# Input2.net
KiCad netlist of a schematic drawn in Altium Designer
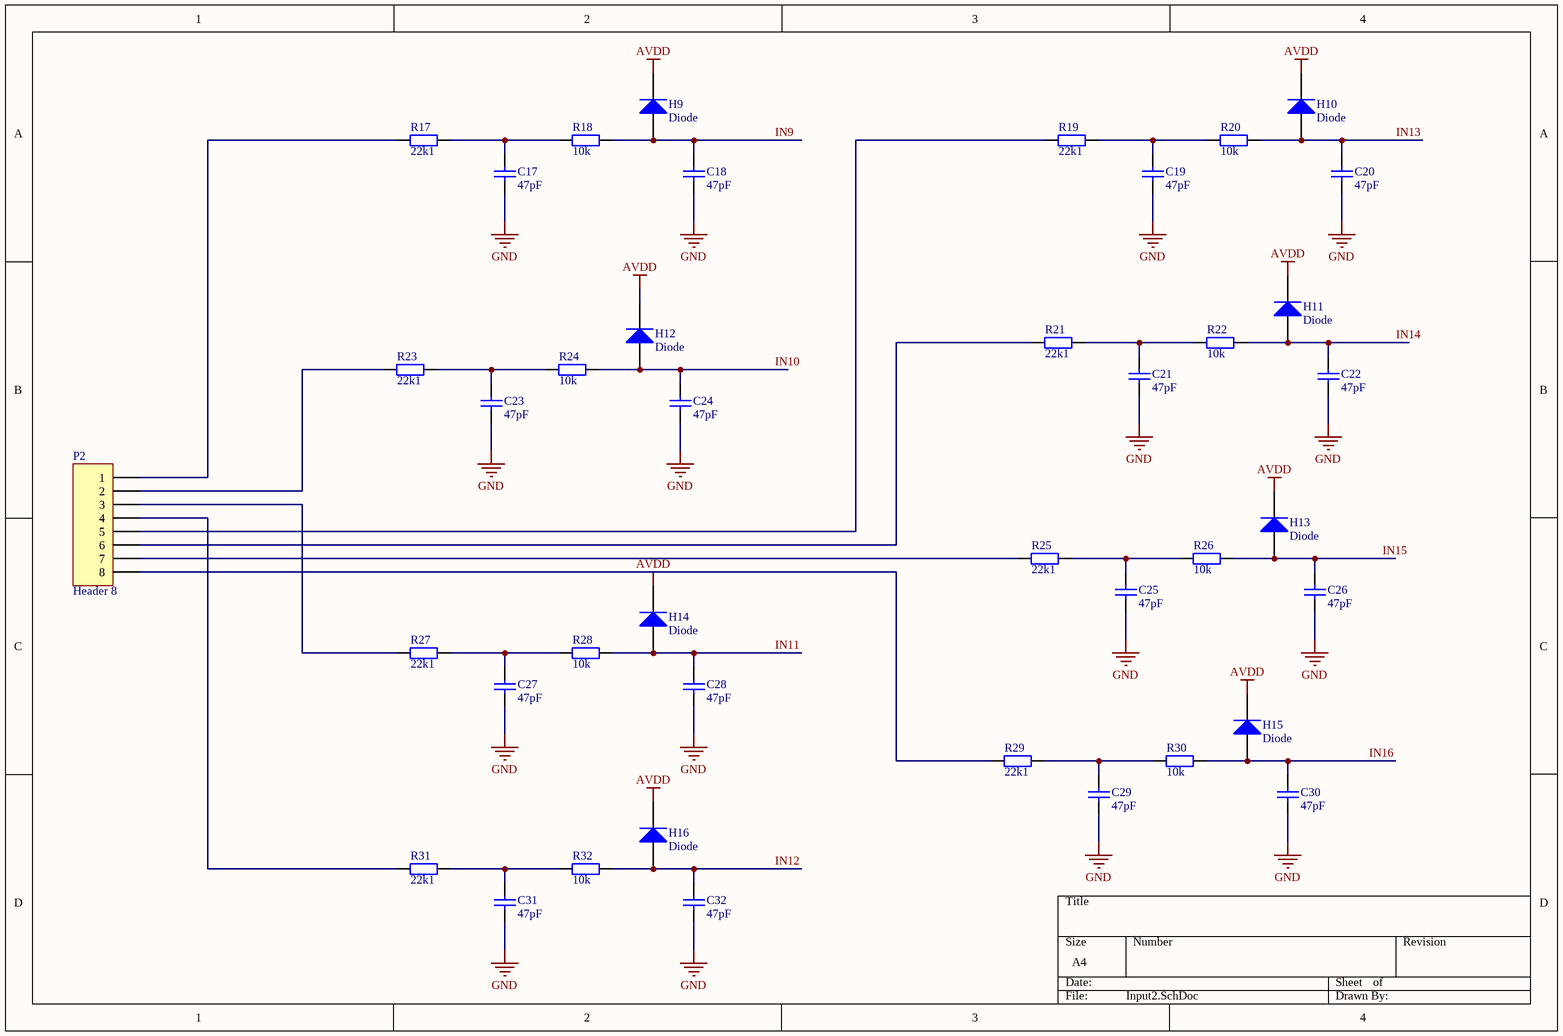
[diagram p0: Input2.SchDoc]

(export (version "E")
  (design (tool "Eeschema 10.0.6"))
  (components
    (comp (ref "C17")
      (value "47pF")
      (footprint "RAD-0.3")
      (description "Capacitor")
      (fields (field (name "PUBLISHER") "Altium Limited"))
      (libsource (lib "Miscellaneous Devices") (part "Cap"))
    )
    (comp (ref "C18")
      (value "47pF")
      (footprint "RAD-0.3")
      (description "Capacitor")
      (fields (field (name "PUBLISHER") "Altium Limited"))
      (libsource (lib "Miscellaneous Devices") (part "Cap"))
    )
    (comp (ref "C19")
      (value "47pF")
      (footprint "RAD-0.3")
      (description "Capacitor")
      (fields (field (name "PUBLISHER") "Altium Limited"))
      (libsource (lib "Miscellaneous Devices") (part "Cap"))
    )
    (comp (ref "C20")
      (value "47pF")
      (footprint "RAD-0.3")
      (description "Capacitor")
      (fields (field (name "PUBLISHER") "Altium Limited"))
      (libsource (lib "Miscellaneous Devices") (part "Cap"))
    )
    (comp (ref "C21")
      (value "47pF")
      (footprint "RAD-0.3")
      (description "Capacitor")
      (fields (field (name "PUBLISHER") "Altium Limited"))
      (libsource (lib "Miscellaneous Devices") (part "Cap"))
    )
    (comp (ref "C22")
      (value "47pF")
      (footprint "RAD-0.3")
      (description "Capacitor")
      (fields (field (name "PUBLISHER") "Altium Limited"))
      (libsource (lib "Miscellaneous Devices") (part "Cap"))
    )
    (comp (ref "C23")
      (value "47pF")
      (footprint "RAD-0.3")
      (description "Capacitor")
      (fields (field (name "PUBLISHER") "Altium Limited"))
      (libsource (lib "Miscellaneous Devices") (part "Cap"))
    )
    (comp (ref "C24")
      (value "47pF")
      (footprint "RAD-0.3")
      (description "Capacitor")
      (fields (field (name "PUBLISHER") "Altium Limited"))
      (libsource (lib "Miscellaneous Devices") (part "Cap"))
    )
    (comp (ref "C25")
      (value "47pF")
      (footprint "RAD-0.3")
      (description "Capacitor")
      (fields (field (name "PUBLISHER") "Altium Limited"))
      (libsource (lib "Miscellaneous Devices") (part "Cap"))
    )
    (comp (ref "C26")
      (value "47pF")
      (footprint "RAD-0.3")
      (description "Capacitor")
      (fields (field (name "PUBLISHER") "Altium Limited"))
      (libsource (lib "Miscellaneous Devices") (part "Cap"))
    )
    (comp (ref "C27")
      (value "47pF")
      (footprint "RAD-0.3")
      (description "Capacitor")
      (fields (field (name "PUBLISHER") "Altium Limited"))
      (libsource (lib "Miscellaneous Devices") (part "Cap"))
    )
    (comp (ref "C28")
      (value "47pF")
      (footprint "RAD-0.3")
      (description "Capacitor")
      (fields (field (name "PUBLISHER") "Altium Limited"))
      (libsource (lib "Miscellaneous Devices") (part "Cap"))
    )
    (comp (ref "C29")
      (value "47pF")
      (footprint "RAD-0.3")
      (description "Capacitor")
      (fields (field (name "PUBLISHER") "Altium Limited"))
      (libsource (lib "Miscellaneous Devices") (part "Cap"))
    )
    (comp (ref "C30")
      (value "47pF")
      (footprint "RAD-0.3")
      (description "Capacitor")
      (fields (field (name "PUBLISHER") "Altium Limited"))
      (libsource (lib "Miscellaneous Devices") (part "Cap"))
    )
    (comp (ref "C31")
      (value "47pF")
      (footprint "RAD-0.3")
      (description "Capacitor")
      (fields (field (name "PUBLISHER") "Altium Limited"))
      (libsource (lib "Miscellaneous Devices") (part "Cap"))
    )
    (comp (ref "C32")
      (value "47pF")
      (footprint "RAD-0.3")
      (description "Capacitor")
      (fields (field (name "PUBLISHER") "Altium Limited"))
      (libsource (lib "Miscellaneous Devices") (part "Cap"))
    )
    (comp (ref "H9")
      (value "Diode")
      (footprint "SMC")
      (description "Default Diode")
      (fields (field (name "PUBLISHER") "Altium Limited"))
      (libsource (lib "Miscellaneous Devices") (part "Diode"))
    )
    (comp (ref "H10")
      (value "Diode")
      (footprint "SMC")
      (description "Default Diode")
      (fields (field (name "PUBLISHER") "Altium Limited"))
      (libsource (lib "Miscellaneous Devices") (part "Diode"))
    )
    (comp (ref "H11")
      (value "Diode")
      (footprint "SMC")
      (description "Default Diode")
      (fields (field (name "PUBLISHER") "Altium Limited"))
      (libsource (lib "Miscellaneous Devices") (part "Diode"))
    )
    (comp (ref "H12")
      (value "Diode")
      (footprint "SMC")
      (description "Default Diode")
      (fields (field (name "PUBLISHER") "Altium Limited"))
      (libsource (lib "Miscellaneous Devices") (part "Diode"))
    )
    (comp (ref "H13")
      (value "Diode")
      (footprint "SMC")
      (description "Default Diode")
      (fields (field (name "PUBLISHER") "Altium Limited"))
      (libsource (lib "Miscellaneous Devices") (part "Diode"))
    )
    (comp (ref "H14")
      (value "Diode")
      (footprint "SMC")
      (description "Default Diode")
      (fields (field (name "PUBLISHER") "Altium Limited"))
      (libsource (lib "Miscellaneous Devices") (part "Diode"))
    )
    (comp (ref "H15")
      (value "Diode")
      (footprint "SMC")
      (description "Default Diode")
      (fields (field (name "PUBLISHER") "Altium Limited"))
      (libsource (lib "Miscellaneous Devices") (part "Diode"))
    )
    (comp (ref "H16")
      (value "Diode")
      (footprint "SMC")
      (description "Default Diode")
      (fields (field (name "PUBLISHER") "Altium Limited"))
      (libsource (lib "Miscellaneous Devices") (part "Diode"))
    )
    (comp (ref "P2")
      (value "Header 8")
      (footprint "HDR1X8")
      (description "Header, 8-Pin")
      (fields (field (name "PUBLISHER") "Altium Limited"))
      (libsource (lib "Miscellaneous Connectors") (part "Header 8"))
    )
    (comp (ref "R17")
      (value "22k1")
      (footprint "AXIAL-0.4")
      (description "Resistor")
      (fields (field (name "PUBLISHER") "Altium Limited"))
      (libsource (lib "Miscellaneous Devices") (part "Res2"))
    )
    (comp (ref "R18")
      (value "10k")
      (footprint "AXIAL-0.4")
      (description "Resistor")
      (fields (field (name "PUBLISHER") "Altium Limited"))
      (libsource (lib "Miscellaneous Devices") (part "Res2"))
    )
    (comp (ref "R19")
      (value "22k1")
      (footprint "AXIAL-0.4")
      (description "Resistor")
      (fields (field (name "PUBLISHER") "Altium Limited"))
      (libsource (lib "Miscellaneous Devices") (part "Res2"))
    )
    (comp (ref "R20")
      (value "10k")
      (footprint "AXIAL-0.4")
      (description "Resistor")
      (fields (field (name "PUBLISHER") "Altium Limited"))
      (libsource (lib "Miscellaneous Devices") (part "Res2"))
    )
    (comp (ref "R21")
      (value "22k1")
      (footprint "AXIAL-0.4")
      (description "Resistor")
      (fields (field (name "PUBLISHER") "Altium Limited"))
      (libsource (lib "Miscellaneous Devices") (part "Res2"))
    )
    (comp (ref "R22")
      (value "10k")
      (footprint "AXIAL-0.4")
      (description "Resistor")
      (fields (field (name "PUBLISHER") "Altium Limited"))
      (libsource (lib "Miscellaneous Devices") (part "Res2"))
    )
    (comp (ref "R23")
      (value "22k1")
      (footprint "AXIAL-0.4")
      (description "Resistor")
      (fields (field (name "PUBLISHER") "Altium Limited"))
      (libsource (lib "Miscellaneous Devices") (part "Res2"))
    )
    (comp (ref "R24")
      (value "10k")
      (footprint "AXIAL-0.4")
      (description "Resistor")
      (fields (field (name "PUBLISHER") "Altium Limited"))
      (libsource (lib "Miscellaneous Devices") (part "Res2"))
    )
    (comp (ref "R25")
      (value "22k1")
      (footprint "AXIAL-0.4")
      (description "Resistor")
      (fields (field (name "PUBLISHER") "Altium Limited"))
      (libsource (lib "Miscellaneous Devices") (part "Res2"))
    )
    (comp (ref "R26")
      (value "10k")
      (footprint "AXIAL-0.4")
      (description "Resistor")
      (fields (field (name "PUBLISHER") "Altium Limited"))
      (libsource (lib "Miscellaneous Devices") (part "Res2"))
    )
    (comp (ref "R27")
      (value "22k1")
      (footprint "AXIAL-0.4")
      (description "Resistor")
      (fields (field (name "PUBLISHER") "Altium Limited"))
      (libsource (lib "Miscellaneous Devices") (part "Res2"))
    )
    (comp (ref "R28")
      (value "10k")
      (footprint "AXIAL-0.4")
      (description "Resistor")
      (fields (field (name "PUBLISHER") "Altium Limited"))
      (libsource (lib "Miscellaneous Devices") (part "Res2"))
    )
    (comp (ref "R29")
      (value "22k1")
      (footprint "AXIAL-0.4")
      (description "Resistor")
      (fields (field (name "PUBLISHER") "Altium Limited"))
      (libsource (lib "Miscellaneous Devices") (part "Res2"))
    )
    (comp (ref "R30")
      (value "10k")
      (footprint "AXIAL-0.4")
      (description "Resistor")
      (fields (field (name "PUBLISHER") "Altium Limited"))
      (libsource (lib "Miscellaneous Devices") (part "Res2"))
    )
    (comp (ref "R31")
      (value "22k1")
      (footprint "AXIAL-0.4")
      (description "Resistor")
      (fields (field (name "PUBLISHER") "Altium Limited"))
      (libsource (lib "Miscellaneous Devices") (part "Res2"))
    )
    (comp (ref "R32")
      (value "10k")
      (footprint "AXIAL-0.4")
      (description "Resistor")
      (fields (field (name "PUBLISHER") "Altium Limited"))
      (libsource (lib "Miscellaneous Devices") (part "Res2"))
    )
  )
  (nets
    (net (code "1") (name "/IN9") (class "Default")
      (node (ref "C18") (pin "2") (pinfunction "2_2") (pintype "passive"))
      (node (ref "H9") (pin "1") (pinfunction "A_1") (pintype "passive"))
      (node (ref "R18") (pin "2") (pinfunction "2_2") (pintype "passive"))
    )
    (net (code "2") (name "/IN10") (class "Default")
      (node (ref "C24") (pin "2") (pinfunction "2_2") (pintype "passive"))
      (node (ref "H12") (pin "1") (pinfunction "A_1") (pintype "passive"))
      (node (ref "R24") (pin "2") (pinfunction "2_2") (pintype "passive"))
    )
    (net (code "3") (name "/IN11") (class "Default")
      (node (ref "C28") (pin "2") (pinfunction "2_2") (pintype "passive"))
      (node (ref "H14") (pin "1") (pinfunction "A_1") (pintype "passive"))
      (node (ref "R28") (pin "2") (pinfunction "2_2") (pintype "passive"))
    )
    (net (code "4") (name "/IN12") (class "Default")
      (node (ref "C32") (pin "2") (pinfunction "2_2") (pintype "passive"))
      (node (ref "H16") (pin "1") (pinfunction "A_1") (pintype "passive"))
      (node (ref "R32") (pin "2") (pinfunction "2_2") (pintype "passive"))
    )
    (net (code "5") (name "/IN13") (class "Default")
      (node (ref "C20") (pin "2") (pinfunction "2_2") (pintype "passive"))
      (node (ref "H10") (pin "1") (pinfunction "A_1") (pintype "passive"))
      (node (ref "R20") (pin "2") (pinfunction "2_2") (pintype "passive"))
    )
    (net (code "6") (name "/IN14") (class "Default")
      (node (ref "C22") (pin "2") (pinfunction "2_2") (pintype "passive"))
      (node (ref "H11") (pin "1") (pinfunction "A_1") (pintype "passive"))
      (node (ref "R22") (pin "2") (pinfunction "2_2") (pintype "passive"))
    )
    (net (code "7") (name "/IN15") (class "Default")
      (node (ref "C26") (pin "2") (pinfunction "2_2") (pintype "passive"))
      (node (ref "H13") (pin "1") (pinfunction "A_1") (pintype "passive"))
      (node (ref "R26") (pin "2") (pinfunction "2_2") (pintype "passive"))
    )
    (net (code "8") (name "/IN16") (class "Default")
      (node (ref "C30") (pin "2") (pinfunction "2_2") (pintype "passive"))
      (node (ref "H15") (pin "1") (pinfunction "A_1") (pintype "passive"))
      (node (ref "R30") (pin "2") (pinfunction "2_2") (pintype "passive"))
    )
    (net (code "9") (name "AVDD") (class "Default")
      (node (ref "H10") (pin "2") (pinfunction "K_2") (pintype "passive"))
      (node (ref "H11") (pin "2") (pinfunction "K_2") (pintype "passive"))
      (node (ref "H12") (pin "2") (pinfunction "K_2") (pintype "passive"))
      (node (ref "H13") (pin "2") (pinfunction "K_2") (pintype "passive"))
      (node (ref "H14") (pin "2") (pinfunction "K_2") (pintype "passive"))
      (node (ref "H15") (pin "2") (pinfunction "K_2") (pintype "passive"))
      (node (ref "H16") (pin "2") (pinfunction "K_2") (pintype "passive"))
      (node (ref "H9") (pin "2") (pinfunction "K_2") (pintype "passive"))
    )
    (net (code "10") (name "GND") (class "Default")
      (node (ref "C17") (pin "1") (pinfunction "1_1") (pintype "passive"))
      (node (ref "C18") (pin "1") (pinfunction "1_1") (pintype "passive"))
      (node (ref "C19") (pin "1") (pinfunction "1_1") (pintype "passive"))
      (node (ref "C20") (pin "1") (pinfunction "1_1") (pintype "passive"))
      (node (ref "C21") (pin "1") (pinfunction "1_1") (pintype "passive"))
      (node (ref "C22") (pin "1") (pinfunction "1_1") (pintype "passive"))
      (node (ref "C23") (pin "1") (pinfunction "1_1") (pintype "passive"))
      (node (ref "C24") (pin "1") (pinfunction "1_1") (pintype "passive"))
      (node (ref "C25") (pin "1") (pinfunction "1_1") (pintype "passive"))
      (node (ref "C26") (pin "1") (pinfunction "1_1") (pintype "passive"))
      (node (ref "C27") (pin "1") (pinfunction "1_1") (pintype "passive"))
      (node (ref "C28") (pin "1") (pinfunction "1_1") (pintype "passive"))
      (node (ref "C29") (pin "1") (pinfunction "1_1") (pintype "passive"))
      (node (ref "C30") (pin "1") (pinfunction "1_1") (pintype "passive"))
      (node (ref "C31") (pin "1") (pinfunction "1_1") (pintype "passive"))
      (node (ref "C32") (pin "1") (pinfunction "1_1") (pintype "passive"))
    )
    (net (code "11") (name "Net-(C17-Pad2)") (class "Default")
      (node (ref "C17") (pin "2") (pinfunction "2_2") (pintype "passive"))
      (node (ref "R17") (pin "2") (pinfunction "2_2") (pintype "passive"))
      (node (ref "R18") (pin "1") (pinfunction "1_1") (pintype "passive"))
    )
    (net (code "12") (name "Net-(C19-Pad2)") (class "Default")
      (node (ref "C19") (pin "2") (pinfunction "2_2") (pintype "passive"))
      (node (ref "R19") (pin "2") (pinfunction "2_2") (pintype "passive"))
      (node (ref "R20") (pin "1") (pinfunction "1_1") (pintype "passive"))
    )
    (net (code "13") (name "Net-(C21-Pad2)") (class "Default")
      (node (ref "C21") (pin "2") (pinfunction "2_2") (pintype "passive"))
      (node (ref "R21") (pin "2") (pinfunction "2_2") (pintype "passive"))
      (node (ref "R22") (pin "1") (pinfunction "1_1") (pintype "passive"))
    )
    (net (code "14") (name "Net-(C23-Pad2)") (class "Default")
      (node (ref "C23") (pin "2") (pinfunction "2_2") (pintype "passive"))
      (node (ref "R23") (pin "2") (pinfunction "2_2") (pintype "passive"))
      (node (ref "R24") (pin "1") (pinfunction "1_1") (pintype "passive"))
    )
    (net (code "15") (name "Net-(C25-Pad2)") (class "Default")
      (node (ref "C25") (pin "2") (pinfunction "2_2") (pintype "passive"))
      (node (ref "R25") (pin "2") (pinfunction "2_2") (pintype "passive"))
      (node (ref "R26") (pin "1") (pinfunction "1_1") (pintype "passive"))
    )
    (net (code "16") (name "Net-(C27-Pad2)") (class "Default")
      (node (ref "C27") (pin "2") (pinfunction "2_2") (pintype "passive"))
      (node (ref "R27") (pin "2") (pinfunction "2_2") (pintype "passive"))
      (node (ref "R28") (pin "1") (pinfunction "1_1") (pintype "passive"))
    )
    (net (code "17") (name "Net-(C29-Pad2)") (class "Default")
      (node (ref "C29") (pin "2") (pinfunction "2_2") (pintype "passive"))
      (node (ref "R29") (pin "2") (pinfunction "2_2") (pintype "passive"))
      (node (ref "R30") (pin "1") (pinfunction "1_1") (pintype "passive"))
    )
    (net (code "18") (name "Net-(C31-Pad2)") (class "Default")
      (node (ref "C31") (pin "2") (pinfunction "2_2") (pintype "passive"))
      (node (ref "R31") (pin "2") (pinfunction "2_2") (pintype "passive"))
      (node (ref "R32") (pin "1") (pinfunction "1_1") (pintype "passive"))
    )
    (net (code "19") (name "Net-(P2-Pad1)") (class "Default")
      (node (ref "P2") (pin "1") (pinfunction "1_1") (pintype "passive"))
      (node (ref "R17") (pin "1") (pinfunction "1_1") (pintype "passive"))
    )
    (net (code "20") (name "Net-(P2-Pad2)") (class "Default")
      (node (ref "P2") (pin "2") (pinfunction "2_2") (pintype "passive"))
      (node (ref "R23") (pin "1") (pinfunction "1_1") (pintype "passive"))
    )
    (net (code "21") (name "Net-(P2-Pad3)") (class "Default")
      (node (ref "P2") (pin "3") (pinfunction "3_3") (pintype "passive"))
      (node (ref "R27") (pin "1") (pinfunction "1_1") (pintype "passive"))
    )
    (net (code "22") (name "Net-(P2-Pad4)") (class "Default")
      (node (ref "P2") (pin "4") (pinfunction "4_4") (pintype "passive"))
      (node (ref "R31") (pin "1") (pinfunction "1_1") (pintype "passive"))
    )
    (net (code "23") (name "Net-(P2-Pad5)") (class "Default")
      (node (ref "P2") (pin "5") (pinfunction "5_5") (pintype "passive"))
      (node (ref "R19") (pin "1") (pinfunction "1_1") (pintype "passive"))
    )
    (net (code "24") (name "Net-(P2-Pad6)") (class "Default")
      (node (ref "P2") (pin "6") (pinfunction "6_6") (pintype "passive"))
      (node (ref "R21") (pin "1") (pinfunction "1_1") (pintype "passive"))
    )
    (net (code "25") (name "Net-(P2-Pad7)") (class "Default")
      (node (ref "P2") (pin "7") (pinfunction "7_7") (pintype "passive"))
      (node (ref "R25") (pin "1") (pinfunction "1_1") (pintype "passive"))
    )
    (net (code "26") (name "Net-(P2-Pad8)") (class "Default")
      (node (ref "P2") (pin "8") (pinfunction "8_8") (pintype "passive"))
      (node (ref "R29") (pin "1") (pinfunction "1_1") (pintype "passive"))
    )
  )
)
